# RGBLedDimmer.net
KiCad netlist of a schematic drawn in EAGLE
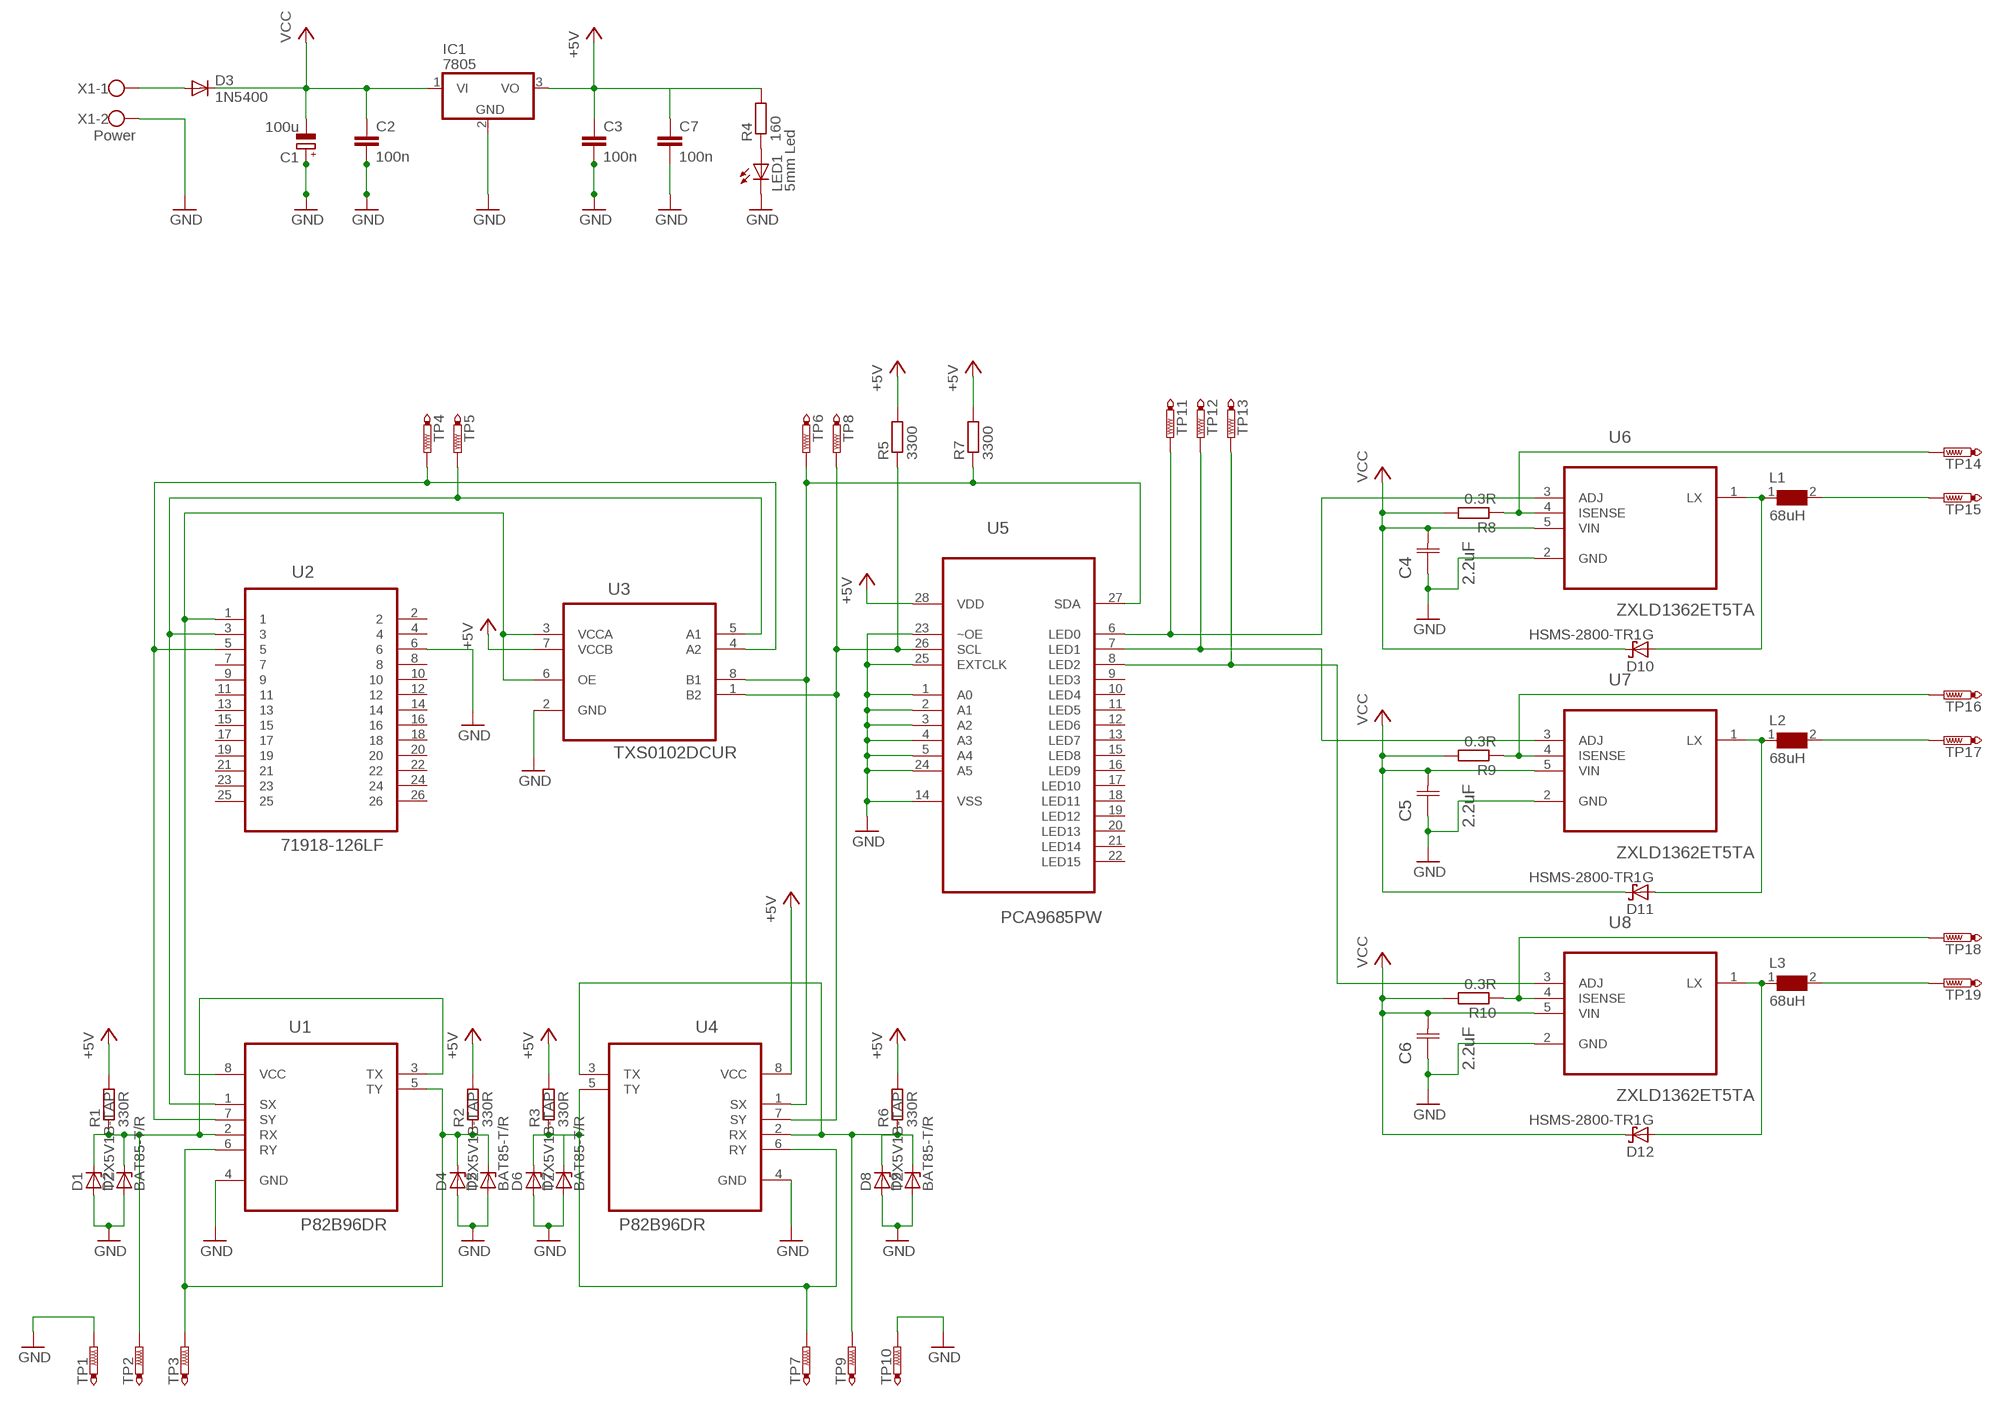
[diagram p0: schematic, sheet 1]

(export (version "E")
  (design (tool "Eeschema 10.0.6"))
  (components
    (comp (ref "C1")
      (value "100u")
      (footprint "eagle-import:E3,5-8")
      (libsource (lib "eagle-import") (part "CPOL-EUE3.5-8"))
    )
    (comp (ref "C2")
      (value "100n")
      (footprint "eagle-import:C025_050-025X075")
      (libsource (lib "eagle-import") (part "C-EU025_050-025X075"))
    )
    (comp (ref "C3")
      (value "100n")
      (footprint "eagle-import:C025_050-025X075")
      (libsource (lib "eagle-import") (part "C-EU025_050-025X075"))
    )
    (comp (ref "C4")
      (value "2.2uF")
      (footprint "eagle-import:CAPC2013X152N")
      (fields (field (name "MPN") "08053C225KAT2A") (field (name "TOLERANCE") "±10%"))
      (libsource (lib "eagle-import") (part "08053C225KAT2A"))
    )
    (comp (ref "C5")
      (value "2.2uF")
      (footprint "eagle-import:CAPC2013X152N")
      (fields (field (name "MPN") "08053C225KAT2A") (field (name "TOLERANCE") "±10%"))
      (libsource (lib "eagle-import") (part "08053C225KAT2A"))
    )
    (comp (ref "C6")
      (value "2.2uF")
      (footprint "eagle-import:CAPC2013X152N")
      (fields (field (name "MPN") "08053C225KAT2A") (field (name "TOLERANCE") "±10%"))
      (libsource (lib "eagle-import") (part "08053C225KAT2A"))
    )
    (comp (ref "C7")
      (value "100n")
      (footprint "eagle-import:C025_050-025X075")
      (libsource (lib "eagle-import") (part "C-EU025_050-025X075"))
    )
    (comp (ref "D1")
      (value "TZX5V1B-TAP")
      (footprint "eagle-import:DO34Z7")
      (libsource (lib "eagle-import") (part "ZENER-DIODEDO34-7"))
    )
    (comp (ref "D2")
      (value "BAT85-T/R")
      (footprint "eagle-import:DO34Z7")
      (libsource (lib "eagle-import") (part "ZENER-DIODEDO34-7"))
    )
    (comp (ref "D3")
      (value "1N5400")
      (footprint "eagle-import:DO201-15")
      (libsource (lib "eagle-import") (part "1N5400"))
    )
    (comp (ref "D4")
      (value "TZX5V1B-TAP")
      (footprint "eagle-import:DO34Z7")
      (libsource (lib "eagle-import") (part "ZENER-DIODEDO34-7"))
    )
    (comp (ref "D5")
      (value "BAT85-T/R")
      (footprint "eagle-import:DO34Z7")
      (libsource (lib "eagle-import") (part "ZENER-DIODEDO34-7"))
    )
    (comp (ref "D6")
      (value "TZX5V1B-TAP")
      (footprint "eagle-import:DO34Z7")
      (libsource (lib "eagle-import") (part "ZENER-DIODEDO34-7"))
    )
    (comp (ref "D7")
      (value "BAT85-T/R")
      (footprint "eagle-import:DO34Z7")
      (libsource (lib "eagle-import") (part "ZENER-DIODEDO34-7"))
    )
    (comp (ref "D8")
      (value "TZX5V1B-TAP")
      (footprint "eagle-import:DO34Z7")
      (libsource (lib "eagle-import") (part "ZENER-DIODEDO34-7"))
    )
    (comp (ref "D9")
      (value "BAT85-T/R")
      (footprint "eagle-import:DO34Z7")
      (libsource (lib "eagle-import") (part "ZENER-DIODEDO34-7"))
    )
    (comp (ref "D10")
      (value "HSMS-2800-TR1G")
      (footprint "eagle-import:SOT23")
      (libsource (lib "eagle-import") (part "BAS70"))
    )
    (comp (ref "D11")
      (value "HSMS-2800-TR1G")
      (footprint "eagle-import:SOT23")
      (libsource (lib "eagle-import") (part "BAS70"))
    )
    (comp (ref "D12")
      (value "HSMS-2800-TR1G")
      (footprint "eagle-import:SOT23")
      (libsource (lib "eagle-import") (part "BAS70"))
    )
    (comp (ref "IC1")
      (value "7805")
      (footprint "eagle-import:TO220V")
      (libsource (lib "eagle-import") (part "78TV12"))
    )
    (comp (ref "L1")
      (value "68uH")
      (footprint "eagle-import:L")
      (fields (field (name "MPN") "74456168"))
      (libsource (lib "eagle-import") (part "WE-PD4_L-74456168"))
    )
    (comp (ref "L2")
      (value "68uH")
      (footprint "eagle-import:L")
      (fields (field (name "MPN") "74456168"))
      (libsource (lib "eagle-import") (part "WE-PD4_L-74456168"))
    )
    (comp (ref "L3")
      (value "68uH")
      (footprint "eagle-import:L")
      (fields (field (name "MPN") "74456168"))
      (libsource (lib "eagle-import") (part "WE-PD4_L-74456168"))
    )
    (comp (ref "LED1")
      (value "5mm Led")
      (footprint "eagle-import:LED5MM")
      (libsource (lib "eagle-import") (part "LED5MM"))
    )
    (comp (ref "R1")
      (value "330R")
      (footprint "eagle-import:0204_7")
      (libsource (lib "eagle-import") (part "R-EU_0204/7"))
    )
    (comp (ref "R2")
      (value "330R")
      (footprint "eagle-import:0204_7")
      (libsource (lib "eagle-import") (part "R-EU_0204/7"))
    )
    (comp (ref "R3")
      (value "330R")
      (footprint "eagle-import:0204_7")
      (libsource (lib "eagle-import") (part "R-EU_0204/7"))
    )
    (comp (ref "R4")
      (value "160")
      (footprint "eagle-import:0204_7")
      (libsource (lib "eagle-import") (part "R-EU_0204/7"))
    )
    (comp (ref "R5")
      (value "3300")
      (footprint "eagle-import:0204_7")
      (libsource (lib "eagle-import") (part "R-EU_0204/7"))
    )
    (comp (ref "R6")
      (value "330R")
      (footprint "eagle-import:0204_7")
      (libsource (lib "eagle-import") (part "R-EU_0204/7"))
    )
    (comp (ref "R7")
      (value "3300")
      (footprint "eagle-import:0204_7")
      (libsource (lib "eagle-import") (part "R-EU_0204/7"))
    )
    (comp (ref "R8")
      (value "0.3R")
      (footprint "eagle-import:R0603")
      (libsource (lib "eagle-import") (part "resistor_R-EU_R0603"))
    )
    (comp (ref "R9")
      (value "0.3R")
      (footprint "eagle-import:R0603")
      (libsource (lib "eagle-import") (part "resistor_R-EU_R0603"))
    )
    (comp (ref "R10")
      (value "0.3R")
      (footprint "eagle-import:R0603")
      (libsource (lib "eagle-import") (part "resistor_R-EU_R0603"))
    )
    (comp (ref "TP1")
      (value "PTR1PAD1-13")
      (footprint "eagle-import:P1-13")
      (libsource (lib "eagle-import") (part "PTR1PAD1-13"))
    )
    (comp (ref "TP2")
      (value "PTR1PAD1-13")
      (footprint "eagle-import:P1-13")
      (libsource (lib "eagle-import") (part "PTR1PAD1-13"))
    )
    (comp (ref "TP3")
      (value "PTR1PAD1-13")
      (footprint "eagle-import:P1-13")
      (libsource (lib "eagle-import") (part "PTR1PAD1-13"))
    )
    (comp (ref "TP4")
      (value "PTR1PAD1-13")
      (footprint "eagle-import:P1-13")
      (libsource (lib "eagle-import") (part "PTR1PAD1-13"))
    )
    (comp (ref "TP5")
      (value "PTR1PAD1-13")
      (footprint "eagle-import:P1-13")
      (libsource (lib "eagle-import") (part "PTR1PAD1-13"))
    )
    (comp (ref "TP6")
      (value "PTR1PAD1-13")
      (footprint "eagle-import:P1-13")
      (libsource (lib "eagle-import") (part "PTR1PAD1-13"))
    )
    (comp (ref "TP7")
      (value "PTR1PAD1-13")
      (footprint "eagle-import:P1-13")
      (libsource (lib "eagle-import") (part "PTR1PAD1-13"))
    )
    (comp (ref "TP8")
      (value "PTR1PAD1-13")
      (footprint "eagle-import:P1-13")
      (libsource (lib "eagle-import") (part "PTR1PAD1-13"))
    )
    (comp (ref "TP9")
      (value "PTR1PAD1-13")
      (footprint "eagle-import:P1-13")
      (libsource (lib "eagle-import") (part "PTR1PAD1-13"))
    )
    (comp (ref "TP10")
      (value "PTR1PAD1-13")
      (footprint "eagle-import:P1-13")
      (libsource (lib "eagle-import") (part "PTR1PAD1-13"))
    )
    (comp (ref "TP11")
      (value "PTR1PAD1-13")
      (footprint "eagle-import:P1-13")
      (libsource (lib "eagle-import") (part "PTR1PAD1-13"))
    )
    (comp (ref "TP12")
      (value "PTR1PAD1-13")
      (footprint "eagle-import:P1-13")
      (libsource (lib "eagle-import") (part "PTR1PAD1-13"))
    )
    (comp (ref "TP13")
      (value "PTR1PAD1-13")
      (footprint "eagle-import:P1-13")
      (libsource (lib "eagle-import") (part "PTR1PAD1-13"))
    )
    (comp (ref "TP14")
      (value "PTR1PAD1-13")
      (footprint "eagle-import:P1-13")
      (libsource (lib "eagle-import") (part "PTR1PAD1-13"))
    )
    (comp (ref "TP15")
      (value "PTR1PAD1-13")
      (footprint "eagle-import:P1-13")
      (libsource (lib "eagle-import") (part "PTR1PAD1-13"))
    )
    (comp (ref "TP16")
      (value "PTR1PAD1-13")
      (footprint "eagle-import:P1-13")
      (libsource (lib "eagle-import") (part "PTR1PAD1-13"))
    )
    (comp (ref "TP17")
      (value "PTR1PAD1-13")
      (footprint "eagle-import:P1-13")
      (libsource (lib "eagle-import") (part "PTR1PAD1-13"))
    )
    (comp (ref "TP18")
      (value "PTR1PAD1-13")
      (footprint "eagle-import:P1-13")
      (libsource (lib "eagle-import") (part "PTR1PAD1-13"))
    )
    (comp (ref "TP19")
      (value "PTR1PAD1-13")
      (footprint "eagle-import:P1-13")
      (libsource (lib "eagle-import") (part "PTR1PAD1-13"))
    )
    (comp (ref "U1")
      (value "P82B96DR")
      (footprint "eagle-import:SOIC127P600X175-8N")
      (libsource (lib "eagle-import") (part "P82B96DR"))
    )
    (comp (ref "U2")
      (value "71918-126LF")
      (footprint "eagle-import:FCI_71918-126LF")
      (libsource (lib "eagle-import") (part "71918-126LF"))
    )
    (comp (ref "U3")
      (value "TXS0102DCUR")
      (footprint "eagle-import:SOP50P310X90-8N")
      (libsource (lib "eagle-import") (part "TXS0102DCUR"))
    )
    (comp (ref "U4")
      (value "P82B96DR")
      (footprint "eagle-import:SOIC127P600X175-8N")
      (libsource (lib "eagle-import") (part "P82B96DR"))
    )
    (comp (ref "U5")
      (value "PCA9685PW")
      (footprint "eagle-import:SOP65P640X110-28N")
      (libsource (lib "eagle-import") (part "PCA9685PW"))
    )
    (comp (ref "U6")
      (value "ZXLD1362ET5TA")
      (footprint "eagle-import:SOT95P270X145-5N")
      (libsource (lib "eagle-import") (part "ZXLD1362ET5TA"))
    )
    (comp (ref "U7")
      (value "ZXLD1362ET5TA")
      (footprint "eagle-import:SOT95P270X145-5N")
      (libsource (lib "eagle-import") (part "ZXLD1362ET5TA"))
    )
    (comp (ref "U8")
      (value "ZXLD1362ET5TA")
      (footprint "eagle-import:SOT95P270X145-5N")
      (libsource (lib "eagle-import") (part "ZXLD1362ET5TA"))
    )
    (comp (ref "X1")
      (value "Power")
      (footprint "eagle-import:W237-102")
      (fields (field (name "MPN") "237-102"))
      (libsource (lib "eagle-import") (part "W237-102"))
    )
  )
  (nets
    (net (code "1") (name "+5V") (class "Default")
      (node (ref "C3") (pin "1") (pinfunction "1_1") (pintype "passive"))
      (node (ref "C7") (pin "1") (pinfunction "1_1") (pintype "passive"))
      (node (ref "IC1") (pin "3") (pinfunction "VO_3") (pintype "passive"))
      (node (ref "R1") (pin "2") (pinfunction "2_2") (pintype "passive"))
      (node (ref "R2") (pin "2") (pinfunction "2_2") (pintype "passive"))
      (node (ref "R3") (pin "2") (pinfunction "2_2") (pintype "passive"))
      (node (ref "R4") (pin "2") (pinfunction "2_2") (pintype "passive"))
      (node (ref "R5") (pin "2") (pinfunction "2_2") (pintype "passive"))
      (node (ref "R6") (pin "2") (pinfunction "2_2") (pintype "passive"))
      (node (ref "R7") (pin "2") (pinfunction "2_2") (pintype "passive"))
      (node (ref "U3") (pin "7") (pinfunction "VCCB_7") (pintype "power_in"))
      (node (ref "U4") (pin "8") (pinfunction "VCC_8") (pintype "power_in"))
      (node (ref "U5") (pin "28") (pinfunction "VDD_28") (pintype "power_in"))
    )
    (net (code "2") (name "GND") (class "Default")
      (node (ref "C1") (pin "+") (pinfunction "+_+") (pintype "passive"))
      (node (ref "C2") (pin "2") (pinfunction "2_2") (pintype "passive"))
      (node (ref "C3") (pin "2") (pinfunction "2_2") (pintype "passive"))
      (node (ref "C4") (pin "1") (pinfunction "C1_1") (pintype "passive"))
      (node (ref "C5") (pin "1") (pinfunction "C1_1") (pintype "passive"))
      (node (ref "C6") (pin "1") (pinfunction "C1_1") (pintype "passive"))
      (node (ref "C7") (pin "2") (pinfunction "2_2") (pintype "passive"))
      (node (ref "D1") (pin "A") (pinfunction "A_A") (pintype "passive"))
      (node (ref "D2") (pin "A") (pinfunction "A_A") (pintype "passive"))
      (node (ref "D4") (pin "A") (pinfunction "A_A") (pintype "passive"))
      (node (ref "D5") (pin "A") (pinfunction "A_A") (pintype "passive"))
      (node (ref "D6") (pin "A") (pinfunction "A_A") (pintype "passive"))
      (node (ref "D7") (pin "A") (pinfunction "A_A") (pintype "passive"))
      (node (ref "D8") (pin "A") (pinfunction "A_A") (pintype "passive"))
      (node (ref "D9") (pin "A") (pinfunction "A_A") (pintype "passive"))
      (node (ref "IC1") (pin "2") (pinfunction "GND_2") (pintype "passive"))
      (node (ref "LED1") (pin "K") (pinfunction "C_K") (pintype "passive"))
      (node (ref "TP1") (pin "TP") (pinfunction "TP_TP") (pintype "input"))
      (node (ref "TP10") (pin "TP") (pinfunction "TP_TP") (pintype "input"))
      (node (ref "U1") (pin "4") (pinfunction "GND_4") (pintype "passive"))
      (node (ref "U2") (pin "6") (pinfunction "6_6") (pintype "passive"))
      (node (ref "U3") (pin "2") (pinfunction "GND_2") (pintype "passive"))
      (node (ref "U4") (pin "4") (pinfunction "GND_4") (pintype "passive"))
      (node (ref "U5") (pin "1") (pinfunction "A0_1") (pintype "input"))
      (node (ref "U5") (pin "14") (pinfunction "VSS_14") (pintype "passive"))
      (node (ref "U5") (pin "2") (pinfunction "A1_2") (pintype "input"))
      (node (ref "U5") (pin "23") (pinfunction "~{OE}_23") (pintype "input"))
      (node (ref "U5") (pin "24") (pinfunction "A5_24") (pintype "input"))
      (node (ref "U5") (pin "25") (pinfunction "EXTCLK_25") (pintype "input"))
      (node (ref "U5") (pin "3") (pinfunction "A2_3") (pintype "input"))
      (node (ref "U5") (pin "4") (pinfunction "A3_4") (pintype "input"))
      (node (ref "U5") (pin "5") (pinfunction "A4_5") (pintype "input"))
      (node (ref "U6") (pin "2") (pinfunction "GND_2") (pintype "passive"))
      (node (ref "U7") (pin "2") (pinfunction "GND_2") (pintype "passive"))
      (node (ref "U8") (pin "2") (pinfunction "GND_2") (pintype "passive"))
      (node (ref "X1") (pin "2") (pinfunction "KL_2") (pintype "passive"))
    )
    (net (code "3") (name "Net-(D10-A)") (class "Default")
      (node (ref "D10") (pin "1") (pinfunction "A_1") (pintype "passive"))
      (node (ref "L1") (pin "1") (pinfunction "1_1") (pintype "passive"))
      (node (ref "U6") (pin "1") (pinfunction "LX_1") (pintype "output"))
    )
    (net (code "4") (name "Net-(D11-A)") (class "Default")
      (node (ref "D11") (pin "1") (pinfunction "A_1") (pintype "passive"))
      (node (ref "L2") (pin "1") (pinfunction "1_1") (pintype "passive"))
      (node (ref "U7") (pin "1") (pinfunction "LX_1") (pintype "output"))
    )
    (net (code "5") (name "Net-(D12-A)") (class "Default")
      (node (ref "D12") (pin "1") (pinfunction "A_1") (pintype "passive"))
      (node (ref "L3") (pin "1") (pinfunction "1_1") (pintype "passive"))
      (node (ref "U8") (pin "1") (pinfunction "LX_1") (pintype "output"))
    )
    (net (code "6") (name "Net-(L1-Pad2)") (class "Default")
      (node (ref "L1") (pin "2") (pinfunction "2_2") (pintype "passive"))
      (node (ref "TP15") (pin "TP") (pinfunction "TP_TP") (pintype "input"))
    )
    (net (code "7") (name "Net-(L2-Pad2)") (class "Default")
      (node (ref "L2") (pin "2") (pinfunction "2_2") (pintype "passive"))
      (node (ref "TP17") (pin "TP") (pinfunction "TP_TP") (pintype "input"))
    )
    (net (code "8") (name "Net-(L3-Pad2)") (class "Default")
      (node (ref "L3") (pin "2") (pinfunction "2_2") (pintype "passive"))
      (node (ref "TP19") (pin "TP") (pinfunction "TP_TP") (pintype "input"))
    )
    (net (code "9") (name "Net-(LED1-PadA)") (class "Default")
      (node (ref "LED1") (pin "A") (pinfunction "A_A") (pintype "passive"))
      (node (ref "R4") (pin "1") (pinfunction "1_1") (pintype "passive"))
    )
    (net (code "10") (name "Net-(U1-RX)") (class "Default")
      (node (ref "D1") (pin "C") (pinfunction "C_C") (pintype "passive"))
      (node (ref "D2") (pin "C") (pinfunction "C_C") (pintype "passive"))
      (node (ref "R1") (pin "1") (pinfunction "1_1") (pintype "passive"))
      (node (ref "TP2") (pin "TP") (pinfunction "TP_TP") (pintype "input"))
      (node (ref "U1") (pin "2") (pinfunction "RX_2") (pintype "input"))
      (node (ref "U1") (pin "3") (pinfunction "TX_3") (pintype "output"))
    )
    (net (code "11") (name "Net-(U1-RY)") (class "Default")
      (node (ref "D4") (pin "C") (pinfunction "C_C") (pintype "passive"))
      (node (ref "D5") (pin "C") (pinfunction "C_C") (pintype "passive"))
      (node (ref "R2") (pin "1") (pinfunction "1_1") (pintype "passive"))
      (node (ref "TP3") (pin "TP") (pinfunction "TP_TP") (pintype "input"))
      (node (ref "U1") (pin "5") (pinfunction "TY_5") (pintype "output"))
      (node (ref "U1") (pin "6") (pinfunction "RY_6") (pintype "input"))
    )
    (net (code "12") (name "Net-(U1-SX)") (class "Default")
      (node (ref "TP5") (pin "TP") (pinfunction "TP_TP") (pintype "input"))
      (node (ref "U1") (pin "1") (pinfunction "SX_1") (pintype "input"))
      (node (ref "U2") (pin "3") (pinfunction "3_3") (pintype "passive"))
      (node (ref "U3") (pin "5") (pinfunction "A1_5") (pintype "bidirectional"))
    )
    (net (code "13") (name "Net-(U1-SY)") (class "Default")
      (node (ref "TP4") (pin "TP") (pinfunction "TP_TP") (pintype "input"))
      (node (ref "U1") (pin "7") (pinfunction "SY_7") (pintype "input"))
      (node (ref "U2") (pin "5") (pinfunction "5_5") (pintype "passive"))
      (node (ref "U3") (pin "4") (pinfunction "A2_4") (pintype "bidirectional"))
    )
    (net (code "14") (name "Net-(U1-VCC)") (class "Default")
      (node (ref "U1") (pin "8") (pinfunction "VCC_8") (pintype "power_in"))
      (node (ref "U2") (pin "1") (pinfunction "1_1") (pintype "passive"))
      (node (ref "U3") (pin "3") (pinfunction "VCCA_3") (pintype "power_in"))
      (node (ref "U3") (pin "6") (pinfunction "OE_6") (pintype "input"))
    )
    (net (code "15") (name "Net-(U3-B1)") (class "Default")
      (node (ref "R7") (pin "1") (pinfunction "1_1") (pintype "passive"))
      (node (ref "TP6") (pin "TP") (pinfunction "TP_TP") (pintype "input"))
      (node (ref "U3") (pin "8") (pinfunction "B1_8") (pintype "bidirectional"))
      (node (ref "U4") (pin "1") (pinfunction "SX_1") (pintype "input"))
      (node (ref "U5") (pin "27") (pinfunction "SDA_27") (pintype "bidirectional"))
    )
    (net (code "16") (name "Net-(U3-B2)") (class "Default")
      (node (ref "R5") (pin "1") (pinfunction "1_1") (pintype "passive"))
      (node (ref "TP8") (pin "TP") (pinfunction "TP_TP") (pintype "input"))
      (node (ref "U3") (pin "1") (pinfunction "B2_1") (pintype "bidirectional"))
      (node (ref "U4") (pin "7") (pinfunction "SY_7") (pintype "input"))
      (node (ref "U5") (pin "26") (pinfunction "SCL_26") (pintype "input"))
    )
    (net (code "17") (name "Net-(U4-RX)") (class "Default")
      (node (ref "D8") (pin "C") (pinfunction "C_C") (pintype "passive"))
      (node (ref "D9") (pin "C") (pinfunction "C_C") (pintype "passive"))
      (node (ref "R6") (pin "1") (pinfunction "1_1") (pintype "passive"))
      (node (ref "TP9") (pin "TP") (pinfunction "TP_TP") (pintype "input"))
      (node (ref "U4") (pin "2") (pinfunction "RX_2") (pintype "input"))
      (node (ref "U4") (pin "3") (pinfunction "TX_3") (pintype "output"))
    )
    (net (code "18") (name "Net-(U4-RY)") (class "Default")
      (node (ref "D6") (pin "C") (pinfunction "C_C") (pintype "passive"))
      (node (ref "D7") (pin "C") (pinfunction "C_C") (pintype "passive"))
      (node (ref "R3") (pin "1") (pinfunction "1_1") (pintype "passive"))
      (node (ref "TP7") (pin "TP") (pinfunction "TP_TP") (pintype "input"))
      (node (ref "U4") (pin "5") (pinfunction "TY_5") (pintype "output"))
      (node (ref "U4") (pin "6") (pinfunction "RY_6") (pintype "input"))
    )
    (net (code "19") (name "Net-(U5-LED0)") (class "Default")
      (node (ref "TP11") (pin "TP") (pinfunction "TP_TP") (pintype "input"))
      (node (ref "U5") (pin "6") (pinfunction "LED0_6") (pintype "output"))
      (node (ref "U6") (pin "3") (pinfunction "ADJ_3") (pintype "input"))
    )
    (net (code "20") (name "Net-(U5-LED1)") (class "Default")
      (node (ref "TP12") (pin "TP") (pinfunction "TP_TP") (pintype "input"))
      (node (ref "U5") (pin "7") (pinfunction "LED1_7") (pintype "output"))
      (node (ref "U7") (pin "3") (pinfunction "ADJ_3") (pintype "input"))
    )
    (net (code "21") (name "Net-(U5-LED2)") (class "Default")
      (node (ref "TP13") (pin "TP") (pinfunction "TP_TP") (pintype "input"))
      (node (ref "U5") (pin "8") (pinfunction "LED2_8") (pintype "output"))
      (node (ref "U8") (pin "3") (pinfunction "ADJ_3") (pintype "input"))
    )
    (net (code "22") (name "Net-(U6-ISENSE)") (class "Default")
      (node (ref "R8") (pin "1") (pinfunction "1_1") (pintype "passive"))
      (node (ref "TP14") (pin "TP") (pinfunction "TP_TP") (pintype "input"))
      (node (ref "U6") (pin "4") (pinfunction "ISENSE_4") (pintype "input"))
    )
    (net (code "23") (name "Net-(U7-ISENSE)") (class "Default")
      (node (ref "R9") (pin "1") (pinfunction "1_1") (pintype "passive"))
      (node (ref "TP16") (pin "TP") (pinfunction "TP_TP") (pintype "input"))
      (node (ref "U7") (pin "4") (pinfunction "ISENSE_4") (pintype "input"))
    )
    (net (code "24") (name "Net-(U8-ISENSE)") (class "Default")
      (node (ref "R10") (pin "1") (pinfunction "1_1") (pintype "passive"))
      (node (ref "TP18") (pin "TP") (pinfunction "TP_TP") (pintype "input"))
      (node (ref "U8") (pin "4") (pinfunction "ISENSE_4") (pintype "input"))
    )
    (net (code "25") (name "Net-(X1A-KL)") (class "Default")
      (node (ref "D3") (pin "A") (pinfunction "A_A") (pintype "passive"))
      (node (ref "X1") (pin "1") (pinfunction "KL_1") (pintype "passive"))
    )
    (net (code "26") (name "VCC") (class "Default")
      (node (ref "C1") (pin "-") (pinfunction "-_-") (pintype "passive"))
      (node (ref "C2") (pin "1") (pinfunction "1_1") (pintype "passive"))
      (node (ref "C4") (pin "2") (pinfunction "C2_2") (pintype "passive"))
      (node (ref "C5") (pin "2") (pinfunction "C2_2") (pintype "passive"))
      (node (ref "C6") (pin "2") (pinfunction "C2_2") (pintype "passive"))
      (node (ref "D10") (pin "3") (pinfunction "C_3") (pintype "passive"))
      (node (ref "D11") (pin "3") (pinfunction "C_3") (pintype "passive"))
      (node (ref "D12") (pin "3") (pinfunction "C_3") (pintype "passive"))
      (node (ref "D3") (pin "C") (pinfunction "C_C") (pintype "passive"))
      (node (ref "IC1") (pin "1") (pinfunction "VI_1") (pintype "input"))
      (node (ref "R10") (pin "2") (pinfunction "2_2") (pintype "passive"))
      (node (ref "R8") (pin "2") (pinfunction "2_2") (pintype "passive"))
      (node (ref "R9") (pin "2") (pinfunction "2_2") (pintype "passive"))
      (node (ref "U6") (pin "5") (pinfunction "VIN_5") (pintype "input"))
      (node (ref "U7") (pin "5") (pinfunction "VIN_5") (pintype "input"))
      (node (ref "U8") (pin "5") (pinfunction "VIN_5") (pintype "input"))
    )
    (net (code "27") (name "unconnected-(U2-Pad2)") (class "Default")
      (node (ref "U2") (pin "2") (pinfunction "2_2") (pintype "passive"))
    )
    (net (code "28") (name "unconnected-(U2-Pad4)") (class "Default")
      (node (ref "U2") (pin "4") (pinfunction "4_4") (pintype "passive"))
    )
    (net (code "29") (name "unconnected-(U2-Pad7)") (class "Default")
      (node (ref "U2") (pin "7") (pinfunction "7_7") (pintype "passive"))
    )
    (net (code "30") (name "unconnected-(U2-Pad8)") (class "Default")
      (node (ref "U2") (pin "8") (pinfunction "8_8") (pintype "passive"))
    )
    (net (code "31") (name "unconnected-(U2-Pad9)") (class "Default")
      (node (ref "U2") (pin "9") (pinfunction "9_9") (pintype "passive"))
    )
    (net (code "32") (name "unconnected-(U2-Pad10)") (class "Default")
      (node (ref "U2") (pin "10") (pinfunction "10_10") (pintype "passive"))
    )
    (net (code "33") (name "unconnected-(U2-Pad11)") (class "Default")
      (node (ref "U2") (pin "11") (pinfunction "11_11") (pintype "passive"))
    )
    (net (code "34") (name "unconnected-(U2-Pad12)") (class "Default")
      (node (ref "U2") (pin "12") (pinfunction "12_12") (pintype "passive"))
    )
    (net (code "35") (name "unconnected-(U2-Pad13)") (class "Default")
      (node (ref "U2") (pin "13") (pinfunction "13_13") (pintype "passive"))
    )
    (net (code "36") (name "unconnected-(U2-Pad14)") (class "Default")
      (node (ref "U2") (pin "14") (pinfunction "14_14") (pintype "passive"))
    )
    (net (code "37") (name "unconnected-(U2-Pad15)") (class "Default")
      (node (ref "U2") (pin "15") (pinfunction "15_15") (pintype "passive"))
    )
    (net (code "38") (name "unconnected-(U2-Pad16)") (class "Default")
      (node (ref "U2") (pin "16") (pinfunction "16_16") (pintype "passive"))
    )
    (net (code "39") (name "unconnected-(U2-Pad17)") (class "Default")
      (node (ref "U2") (pin "17") (pinfunction "17_17") (pintype "passive"))
    )
    (net (code "40") (name "unconnected-(U2-Pad18)") (class "Default")
      (node (ref "U2") (pin "18") (pinfunction "18_18") (pintype "passive"))
    )
    (net (code "41") (name "unconnected-(U2-Pad19)") (class "Default")
      (node (ref "U2") (pin "19") (pinfunction "19_19") (pintype "passive"))
    )
    (net (code "42") (name "unconnected-(U2-Pad20)") (class "Default")
      (node (ref "U2") (pin "20") (pinfunction "20_20") (pintype "passive"))
    )
    (net (code "43") (name "unconnected-(U2-Pad21)") (class "Default")
      (node (ref "U2") (pin "21") (pinfunction "21_21") (pintype "passive"))
    )
    (net (code "44") (name "unconnected-(U2-Pad22)") (class "Default")
      (node (ref "U2") (pin "22") (pinfunction "22_22") (pintype "passive"))
    )
    (net (code "45") (name "unconnected-(U2-Pad23)") (class "Default")
      (node (ref "U2") (pin "23") (pinfunction "23_23") (pintype "passive"))
    )
    (net (code "46") (name "unconnected-(U2-Pad24)") (class "Default")
      (node (ref "U2") (pin "24") (pinfunction "24_24") (pintype "passive"))
    )
    (net (code "47") (name "unconnected-(U2-Pad25)") (class "Default")
      (node (ref "U2") (pin "25") (pinfunction "25_25") (pintype "passive"))
    )
    (net (code "48") (name "unconnected-(U2-Pad26)") (class "Default")
      (node (ref "U2") (pin "26") (pinfunction "26_26") (pintype "passive"))
    )
    (net (code "49") (name "unconnected-(U5-LED3-Pad9)") (class "Default")
      (node (ref "U5") (pin "9") (pinfunction "LED3_9") (pintype "output"))
    )
    (net (code "50") (name "unconnected-(U5-LED4-Pad10)") (class "Default")
      (node (ref "U5") (pin "10") (pinfunction "LED4_10") (pintype "output"))
    )
    (net (code "51") (name "unconnected-(U5-LED5-Pad11)") (class "Default")
      (node (ref "U5") (pin "11") (pinfunction "LED5_11") (pintype "output"))
    )
    (net (code "52") (name "unconnected-(U5-LED6-Pad12)") (class "Default")
      (node (ref "U5") (pin "12") (pinfunction "LED6_12") (pintype "output"))
    )
    (net (code "53") (name "unconnected-(U5-LED7-Pad13)") (class "Default")
      (node (ref "U5") (pin "13") (pinfunction "LED7_13") (pintype "output"))
    )
    (net (code "54") (name "unconnected-(U5-LED8-Pad15)") (class "Default")
      (node (ref "U5") (pin "15") (pinfunction "LED8_15") (pintype "output"))
    )
    (net (code "55") (name "unconnected-(U5-LED9-Pad16)") (class "Default")
      (node (ref "U5") (pin "16") (pinfunction "LED9_16") (pintype "output"))
    )
    (net (code "56") (name "unconnected-(U5-LED10-Pad17)") (class "Default")
      (node (ref "U5") (pin "17") (pinfunction "LED10_17") (pintype "output"))
    )
    (net (code "57") (name "unconnected-(U5-LED11-Pad18)") (class "Default")
      (node (ref "U5") (pin "18") (pinfunction "LED11_18") (pintype "output"))
    )
    (net (code "58") (name "unconnected-(U5-LED12-Pad19)") (class "Default")
      (node (ref "U5") (pin "19") (pinfunction "LED12_19") (pintype "output"))
    )
    (net (code "59") (name "unconnected-(U5-LED13-Pad20)") (class "Default")
      (node (ref "U5") (pin "20") (pinfunction "LED13_20") (pintype "output"))
    )
    (net (code "60") (name "unconnected-(U5-LED14-Pad21)") (class "Default")
      (node (ref "U5") (pin "21") (pinfunction "LED14_21") (pintype "output"))
    )
    (net (code "61") (name "unconnected-(U5-LED15-Pad22)") (class "Default")
      (node (ref "U5") (pin "22") (pinfunction "LED15_22") (pintype "output"))
    )
  )
)
